# EC.net
KiCad netlist of a schematic drawn in EAGLE
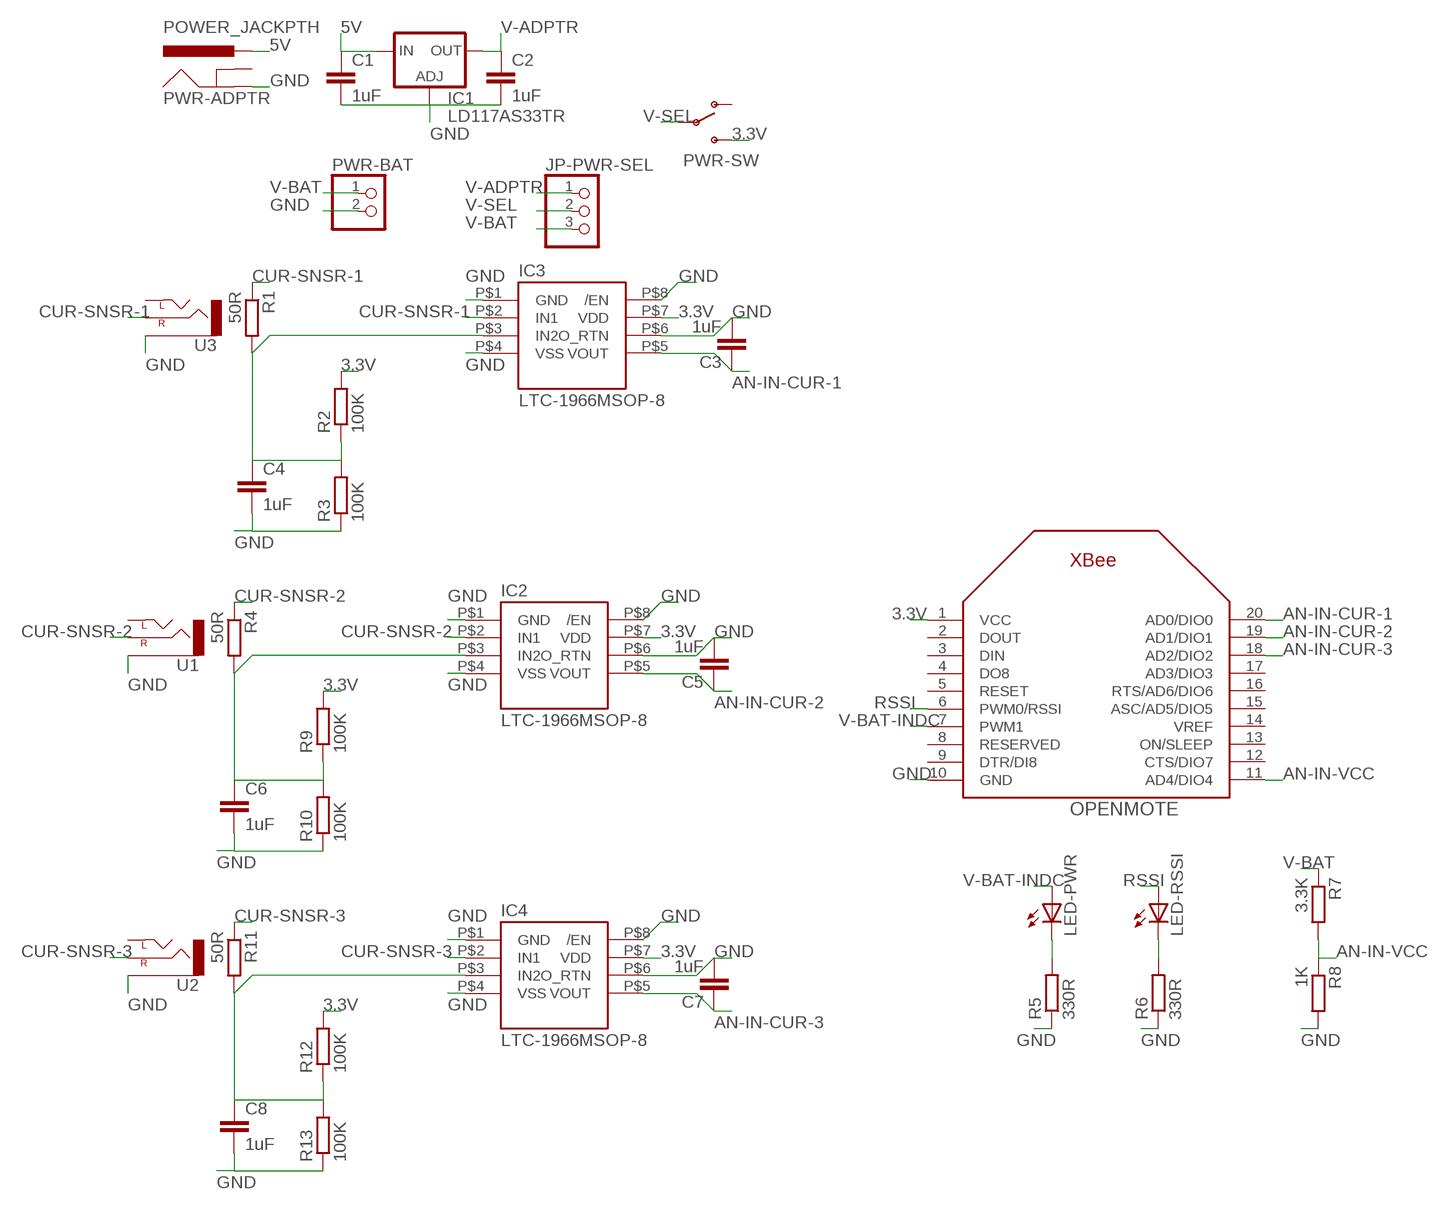
[diagram p0: schematic, sheet 1]

(export (version "E")
  (design (tool "Eeschema 10.0.6"))
  (components
    (comp (ref "C1")
      (value "1uF")
      (footprint "eagle-import:C0805")
      (libsource (lib "eagle-import") (part "C-EUC0805"))
    )
    (comp (ref "C2")
      (value "1uF")
      (footprint "eagle-import:C0805")
      (libsource (lib "eagle-import") (part "C-EUC0805"))
    )
    (comp (ref "C3")
      (value "1uF")
      (footprint "eagle-import:C0805")
      (libsource (lib "eagle-import") (part "C-EUC0805"))
    )
    (comp (ref "C4")
      (value "1uF")
      (footprint "eagle-import:C0805")
      (libsource (lib "eagle-import") (part "C-EUC0805"))
    )
    (comp (ref "C5")
      (value "1uF")
      (footprint "eagle-import:C0805")
      (libsource (lib "eagle-import") (part "C-EUC0805"))
    )
    (comp (ref "C6")
      (value "1uF")
      (footprint "eagle-import:C0805")
      (libsource (lib "eagle-import") (part "C-EUC0805"))
    )
    (comp (ref "C7")
      (value "1uF")
      (footprint "eagle-import:C0805")
      (libsource (lib "eagle-import") (part "C-EUC0805"))
    )
    (comp (ref "C8")
      (value "1uF")
      (footprint "eagle-import:C0805")
      (libsource (lib "eagle-import") (part "C-EUC0805"))
    )
    (comp (ref "IC1")
      (value "LD117AS33TR")
      (footprint "eagle-import:SOT223")
      (libsource (lib "eagle-import") (part "LD117A?S33TR"))
    )
    (comp (ref "IC2")
      (value "LTC-1966MSOP-8")
      (footprint "eagle-import:MSOP-8")
      (libsource (lib "eagle-import") (part "LTC-1966MSOP-8"))
    )
    (comp (ref "IC3")
      (value "LTC-1966MSOP-8")
      (footprint "eagle-import:MSOP-8")
      (libsource (lib "eagle-import") (part "LTC-1966MSOP-8"))
    )
    (comp (ref "IC4")
      (value "LTC-1966MSOP-8")
      (footprint "eagle-import:MSOP-8")
      (libsource (lib "eagle-import") (part "LTC-1966MSOP-8"))
    )
    (comp (ref "JP-PWR-SEL")
      (value "PINHD-1X3")
      (footprint "eagle-import:1X03")
      (libsource (lib "eagle-import") (part "PINHD-1X3"))
    )
    (comp (ref "LED-PWR")
      (value "LED0603")
      (footprint "eagle-import:LED-0603")
      (libsource (lib "eagle-import") (part "LED0603"))
    )
    (comp (ref "LED-RSSI")
      (value "LED0603")
      (footprint "eagle-import:LED-0603")
      (libsource (lib "eagle-import") (part "LED0603"))
    )
    (comp (ref "OPENMOTE")
      (value "XBEE")
      (footprint "eagle-import:XBEE")
      (libsource (lib "eagle-import") (part "XBEE"))
    )
    (comp (ref "PWR-ADPTR")
      (value "POWER_JACKPTH")
      (footprint "eagle-import:POWER_JACK_PTH")
      (libsource (lib "eagle-import") (part "POWER_JACKPTH"))
    )
    (comp (ref "PWR-BAT")
      (value "PINHD-1X2")
      (footprint "eagle-import:1X02")
      (libsource (lib "eagle-import") (part "PINHD-1X2"))
    )
    (comp (ref "PWR-SW")
      (value "SWITCH-SPDTSMD2")
      (footprint "eagle-import:SWITCH-SPDT-SMD")
      (libsource (lib "eagle-import") (part "SWITCH-SPDTSMD2"))
    )
    (comp (ref "R1")
      (value "50R")
      (footprint "eagle-import:R0603")
      (libsource (lib "eagle-import") (part "R-EU_R0603"))
    )
    (comp (ref "R2")
      (value "100K")
      (footprint "eagle-import:R0603")
      (libsource (lib "eagle-import") (part "R-EU_R0603"))
    )
    (comp (ref "R3")
      (value "100K")
      (footprint "eagle-import:R0603")
      (libsource (lib "eagle-import") (part "R-EU_R0603"))
    )
    (comp (ref "R4")
      (value "50R")
      (footprint "eagle-import:R0603")
      (libsource (lib "eagle-import") (part "R-EU_R0603"))
    )
    (comp (ref "R5")
      (value "330R")
      (footprint "eagle-import:R0603")
      (libsource (lib "eagle-import") (part "R-EU_R0603"))
    )
    (comp (ref "R6")
      (value "330R")
      (footprint "eagle-import:R0603")
      (libsource (lib "eagle-import") (part "R-EU_R0603"))
    )
    (comp (ref "R7")
      (value "3.3K")
      (footprint "eagle-import:R0603")
      (libsource (lib "eagle-import") (part "R-EU_R0603"))
    )
    (comp (ref "R8")
      (value "1K")
      (footprint "eagle-import:R0603")
      (libsource (lib "eagle-import") (part "R-EU_R0603"))
    )
    (comp (ref "R9")
      (value "100K")
      (footprint "eagle-import:R0603")
      (libsource (lib "eagle-import") (part "R-EU_R0603"))
    )
    (comp (ref "R10")
      (value "100K")
      (footprint "eagle-import:R0603")
      (libsource (lib "eagle-import") (part "R-EU_R0603"))
    )
    (comp (ref "R11")
      (value "50R")
      (footprint "eagle-import:R0603")
      (libsource (lib "eagle-import") (part "R-EU_R0603"))
    )
    (comp (ref "R12")
      (value "100K")
      (footprint "eagle-import:R0603")
      (libsource (lib "eagle-import") (part "R-EU_R0603"))
    )
    (comp (ref "R13")
      (value "100K")
      (footprint "eagle-import:R0603")
      (libsource (lib "eagle-import") (part "R-EU_R0603"))
    )
    (comp (ref "U1")
      (value "AUDIO-JACKSMD2")
      (footprint "eagle-import:AUDIO-JACK-3.5MM-SMD")
      (libsource (lib "eagle-import") (part "AUDIO-JACKSMD2"))
    )
    (comp (ref "U2")
      (value "AUDIO-JACKSMD2")
      (footprint "eagle-import:AUDIO-JACK-3.5MM-SMD")
      (libsource (lib "eagle-import") (part "AUDIO-JACKSMD2"))
    )
    (comp (ref "U3")
      (value "AUDIO-JACKSMD2")
      (footprint "eagle-import:AUDIO-JACK-3.5MM-SMD")
      (libsource (lib "eagle-import") (part "AUDIO-JACKSMD2"))
    )
  )
  (nets
    (net (code "1") (name "/3.3V") (class "Default")
      (node (ref "IC2") (pin "P$7") (pinfunction "VDD_P$7") (pintype "bidirectional"))
      (node (ref "IC3") (pin "P$7") (pinfunction "VDD_P$7") (pintype "bidirectional"))
      (node (ref "IC4") (pin "P$7") (pinfunction "VDD_P$7") (pintype "bidirectional"))
      (node (ref "OPENMOTE") (pin "1") (pinfunction "VCC_1") (pintype "power_in"))
      (node (ref "PWR-SW") (pin "3") (pinfunction "S_3") (pintype "passive"))
      (node (ref "R12") (pin "2") (pinfunction "2_2") (pintype "passive"))
      (node (ref "R2") (pin "2") (pinfunction "2_2") (pintype "passive"))
      (node (ref "R9") (pin "2") (pinfunction "2_2") (pintype "passive"))
    )
    (net (code "2") (name "/5V") (class "Default")
      (node (ref "C1") (pin "1") (pinfunction "1_1") (pintype "passive"))
      (node (ref "IC1") (pin "3") (pinfunction "IN_3") (pintype "input"))
      (node (ref "PWR-ADPTR") (pin "PWR") (pinfunction "PWR_PWR") (pintype "bidirectional"))
    )
    (net (code "3") (name "/AN-IN-CUR-1") (class "Default")
      (node (ref "C3") (pin "1") (pinfunction "1_1") (pintype "passive"))
      (node (ref "IC3") (pin "P$5") (pinfunction "VOUT_P$5") (pintype "bidirectional"))
      (node (ref "OPENMOTE") (pin "20") (pinfunction "AD0/DIO0_20") (pintype "bidirectional"))
    )
    (net (code "4") (name "/AN-IN-CUR-2") (class "Default")
      (node (ref "C5") (pin "1") (pinfunction "1_1") (pintype "passive"))
      (node (ref "IC2") (pin "P$5") (pinfunction "VOUT_P$5") (pintype "bidirectional"))
      (node (ref "OPENMOTE") (pin "19") (pinfunction "AD1/DIO1_19") (pintype "bidirectional"))
    )
    (net (code "5") (name "/AN-IN-CUR-3") (class "Default")
      (node (ref "C7") (pin "1") (pinfunction "1_1") (pintype "passive"))
      (node (ref "IC4") (pin "P$5") (pinfunction "VOUT_P$5") (pintype "bidirectional"))
      (node (ref "OPENMOTE") (pin "18") (pinfunction "AD2/DIO2_18") (pintype "bidirectional"))
    )
    (net (code "6") (name "/AN-IN-VCC") (class "Default")
      (node (ref "OPENMOTE") (pin "11") (pinfunction "AD4/DIO4_11") (pintype "bidirectional"))
      (node (ref "R7") (pin "2") (pinfunction "2_2") (pintype "passive"))
      (node (ref "R8") (pin "1") (pinfunction "1_1") (pintype "passive"))
    )
    (net (code "7") (name "/CUR-SNSR-1") (class "Default")
      (node (ref "IC3") (pin "P$2") (pinfunction "IN1_P$2") (pintype "bidirectional"))
      (node (ref "R1") (pin "1") (pinfunction "1_1") (pintype "passive"))
      (node (ref "U3") (pin "RING") (pinfunction "RIGHT_RING") (pintype "bidirectional"))
    )
    (net (code "8") (name "/CUR-SNSR-2") (class "Default")
      (node (ref "IC2") (pin "P$2") (pinfunction "IN1_P$2") (pintype "bidirectional"))
      (node (ref "R4") (pin "1") (pinfunction "1_1") (pintype "passive"))
      (node (ref "U1") (pin "RING") (pinfunction "RIGHT_RING") (pintype "bidirectional"))
    )
    (net (code "9") (name "/CUR-SNSR-3") (class "Default")
      (node (ref "IC4") (pin "P$2") (pinfunction "IN1_P$2") (pintype "bidirectional"))
      (node (ref "R11") (pin "1") (pinfunction "1_1") (pintype "passive"))
      (node (ref "U2") (pin "RING") (pinfunction "RIGHT_RING") (pintype "bidirectional"))
    )
    (net (code "10") (name "/GND") (class "Default")
      (node (ref "C1") (pin "2") (pinfunction "2_2") (pintype "passive"))
      (node (ref "C2") (pin "2") (pinfunction "2_2") (pintype "passive"))
      (node (ref "C3") (pin "2") (pinfunction "2_2") (pintype "passive"))
      (node (ref "C4") (pin "2") (pinfunction "2_2") (pintype "passive"))
      (node (ref "C5") (pin "2") (pinfunction "2_2") (pintype "passive"))
      (node (ref "C6") (pin "2") (pinfunction "2_2") (pintype "passive"))
      (node (ref "C7") (pin "2") (pinfunction "2_2") (pintype "passive"))
      (node (ref "C8") (pin "2") (pinfunction "2_2") (pintype "passive"))
      (node (ref "IC1") (pin "1") (pinfunction "ADJ_1") (pintype "input"))
      (node (ref "IC2") (pin "P$1") (pinfunction "GND_P$1") (pintype "bidirectional"))
      (node (ref "IC2") (pin "P$4") (pinfunction "VSS_P$4") (pintype "bidirectional"))
      (node (ref "IC2") (pin "P$6") (pinfunction "O_RTN_P$6") (pintype "bidirectional"))
      (node (ref "IC2") (pin "P$8") (pinfunction "/EN_P$8") (pintype "bidirectional"))
      (node (ref "IC3") (pin "P$1") (pinfunction "GND_P$1") (pintype "bidirectional"))
      (node (ref "IC3") (pin "P$4") (pinfunction "VSS_P$4") (pintype "bidirectional"))
      (node (ref "IC3") (pin "P$6") (pinfunction "O_RTN_P$6") (pintype "bidirectional"))
      (node (ref "IC3") (pin "P$8") (pinfunction "/EN_P$8") (pintype "bidirectional"))
      (node (ref "IC4") (pin "P$1") (pinfunction "GND_P$1") (pintype "bidirectional"))
      (node (ref "IC4") (pin "P$4") (pinfunction "VSS_P$4") (pintype "bidirectional"))
      (node (ref "IC4") (pin "P$6") (pinfunction "O_RTN_P$6") (pintype "bidirectional"))
      (node (ref "IC4") (pin "P$8") (pinfunction "/EN_P$8") (pintype "bidirectional"))
      (node (ref "OPENMOTE") (pin "10") (pinfunction "GND_10") (pintype "power_in"))
      (node (ref "PWR-ADPTR") (pin "GND") (pinfunction "GND_GND") (pintype "bidirectional"))
      (node (ref "PWR-BAT") (pin "2") (pinfunction "2_2") (pintype "passive"))
      (node (ref "R10") (pin "1") (pinfunction "1_1") (pintype "passive"))
      (node (ref "R13") (pin "1") (pinfunction "1_1") (pintype "passive"))
      (node (ref "R3") (pin "1") (pinfunction "1_1") (pintype "passive"))
      (node (ref "R5") (pin "1") (pinfunction "1_1") (pintype "passive"))
      (node (ref "R6") (pin "1") (pinfunction "1_1") (pintype "passive"))
      (node (ref "R8") (pin "2") (pinfunction "2_2") (pintype "passive"))
      (node (ref "U1") (pin "SLEEVE") (pinfunction "SLEEVE_SLEEVE") (pintype "bidirectional"))
      (node (ref "U2") (pin "SLEEVE") (pinfunction "SLEEVE_SLEEVE") (pintype "bidirectional"))
      (node (ref "U3") (pin "SLEEVE") (pinfunction "SLEEVE_SLEEVE") (pintype "bidirectional"))
    )
    (net (code "11") (name "/RSSI") (class "Default")
      (node (ref "LED-RSSI") (pin "A") (pinfunction "A_A") (pintype "passive"))
      (node (ref "OPENMOTE") (pin "6") (pinfunction "PWM0/RSSI_6") (pintype "output"))
    )
    (net (code "12") (name "/V-ADPTR") (class "Default")
      (node (ref "C2") (pin "1") (pinfunction "1_1") (pintype "passive"))
      (node (ref "IC1") (pin "4") (pinfunction "OUT_4") (pintype "passive"))
      (node (ref "JP-PWR-SEL") (pin "1") (pinfunction "1_1") (pintype "passive"))
    )
    (net (code "13") (name "/V-BAT") (class "Default")
      (node (ref "JP-PWR-SEL") (pin "3") (pinfunction "3_3") (pintype "passive"))
      (node (ref "PWR-BAT") (pin "1") (pinfunction "1_1") (pintype "passive"))
      (node (ref "R7") (pin "1") (pinfunction "1_1") (pintype "passive"))
    )
    (net (code "14") (name "/V-BAT-INDC") (class "Default")
      (node (ref "LED-PWR") (pin "A") (pinfunction "A_A") (pintype "passive"))
      (node (ref "OPENMOTE") (pin "7") (pinfunction "PWM1_7") (pintype "output"))
    )
    (net (code "15") (name "/V-SEL") (class "Default")
      (node (ref "JP-PWR-SEL") (pin "2") (pinfunction "2_2") (pintype "passive"))
      (node (ref "PWR-SW") (pin "2") (pinfunction "P_2") (pintype "passive"))
    )
    (net (code "16") (name "Net-(IC2-IN2)") (class "Default")
      (node (ref "C6") (pin "1") (pinfunction "1_1") (pintype "passive"))
      (node (ref "IC2") (pin "P$3") (pinfunction "IN2_P$3") (pintype "bidirectional"))
      (node (ref "R10") (pin "2") (pinfunction "2_2") (pintype "passive"))
      (node (ref "R4") (pin "2") (pinfunction "2_2") (pintype "passive"))
      (node (ref "R9") (pin "1") (pinfunction "1_1") (pintype "passive"))
    )
    (net (code "17") (name "Net-(IC3-IN2)") (class "Default")
      (node (ref "C4") (pin "1") (pinfunction "1_1") (pintype "passive"))
      (node (ref "IC3") (pin "P$3") (pinfunction "IN2_P$3") (pintype "bidirectional"))
      (node (ref "R1") (pin "2") (pinfunction "2_2") (pintype "passive"))
      (node (ref "R2") (pin "1") (pinfunction "1_1") (pintype "passive"))
      (node (ref "R3") (pin "2") (pinfunction "2_2") (pintype "passive"))
    )
    (net (code "18") (name "Net-(IC4-IN2)") (class "Default")
      (node (ref "C8") (pin "1") (pinfunction "1_1") (pintype "passive"))
      (node (ref "IC4") (pin "P$3") (pinfunction "IN2_P$3") (pintype "bidirectional"))
      (node (ref "R11") (pin "2") (pinfunction "2_2") (pintype "passive"))
      (node (ref "R12") (pin "1") (pinfunction "1_1") (pintype "passive"))
      (node (ref "R13") (pin "2") (pinfunction "2_2") (pintype "passive"))
    )
    (net (code "19") (name "Net-(LED-PWR-PadC)") (class "Default")
      (node (ref "LED-PWR") (pin "C") (pinfunction "C_C") (pintype "passive"))
      (node (ref "R5") (pin "2") (pinfunction "2_2") (pintype "passive"))
    )
    (net (code "20") (name "Net-(LED-RSSI-PadC)") (class "Default")
      (node (ref "LED-RSSI") (pin "C") (pinfunction "C_C") (pintype "passive"))
      (node (ref "R6") (pin "2") (pinfunction "2_2") (pintype "passive"))
    )
    (net (code "21") (name "unconnected-(OPENMOTE-AD3{slash}DIO3-Pad17)") (class "Default")
      (node (ref "OPENMOTE") (pin "17") (pinfunction "AD3/DIO3_17") (pintype "bidirectional"))
    )
    (net (code "22") (name "unconnected-(OPENMOTE-ASC{slash}AD5{slash}DIO5-Pad15)") (class "Default")
      (node (ref "OPENMOTE") (pin "15") (pinfunction "ASC/AD5/DIO5_15") (pintype "bidirectional"))
    )
    (net (code "23") (name "unconnected-(OPENMOTE-CTS{slash}DIO7-Pad12)") (class "Default")
      (node (ref "OPENMOTE") (pin "12") (pinfunction "CTS/DIO7_12") (pintype "bidirectional"))
    )
    (net (code "24") (name "unconnected-(OPENMOTE-DIN-Pad3)") (class "Default")
      (node (ref "OPENMOTE") (pin "3") (pinfunction "DIN_3") (pintype "input"))
    )
    (net (code "25") (name "unconnected-(OPENMOTE-DO8-Pad4)") (class "Default")
      (node (ref "OPENMOTE") (pin "4") (pinfunction "DO8_4") (pintype "output"))
    )
    (net (code "26") (name "unconnected-(OPENMOTE-DOUT-Pad2)") (class "Default")
      (node (ref "OPENMOTE") (pin "2") (pinfunction "DOUT_2") (pintype "output"))
    )
    (net (code "27") (name "unconnected-(OPENMOTE-DTR{slash}DI8-Pad9)") (class "Default")
      (node (ref "OPENMOTE") (pin "9") (pinfunction "DTR/DI8_9") (pintype "input"))
    )
    (net (code "28") (name "unconnected-(OPENMOTE-ON{slash}SLEEP-Pad13)") (class "Default")
      (node (ref "OPENMOTE") (pin "13") (pinfunction "ON/SLEEP_13") (pintype "output"))
    )
    (net (code "29") (name "unconnected-(OPENMOTE-RESERVED-Pad8)") (class "Default")
      (node (ref "OPENMOTE") (pin "8") (pinfunction "RESERVED_8") (pintype "no_connect"))
    )
    (net (code "30") (name "unconnected-(OPENMOTE-RESET-Pad5)") (class "Default")
      (node (ref "OPENMOTE") (pin "5") (pinfunction "RESET_5") (pintype "input"))
    )
    (net (code "31") (name "unconnected-(OPENMOTE-RTS{slash}AD6{slash}DIO6-Pad16)") (class "Default")
      (node (ref "OPENMOTE") (pin "16") (pinfunction "RTS/AD6/DIO6_16") (pintype "bidirectional"))
    )
    (net (code "32") (name "unconnected-(OPENMOTE-VREF-Pad14)") (class "Default")
      (node (ref "OPENMOTE") (pin "14") (pinfunction "VREF_14") (pintype "input"))
    )
    (net (code "33") (name "unconnected-(PWR-ADPTR-PadGNDBREAK)") (class "Default")
      (node (ref "PWR-ADPTR") (pin "GNDBREAK") (pinfunction "GNDBREAK_GNDBREAK") (pintype "bidirectional"))
    )
    (net (code "34") (name "unconnected-(PWR-SW-O-Pad1)") (class "Default")
      (node (ref "PWR-SW") (pin "1") (pinfunction "O_1") (pintype "passive"))
    )
    (net (code "35") (name "unconnected-(U1-LEFT-PadTIP)") (class "Default")
      (node (ref "U1") (pin "TIP") (pinfunction "LEFT_TIP") (pintype "bidirectional"))
    )
    (net (code "36") (name "unconnected-(U2-LEFT-PadTIP)") (class "Default")
      (node (ref "U2") (pin "TIP") (pinfunction "LEFT_TIP") (pintype "bidirectional"))
    )
    (net (code "37") (name "unconnected-(U3-LEFT-PadTIP)") (class "Default")
      (node (ref "U3") (pin "TIP") (pinfunction "LEFT_TIP") (pintype "bidirectional"))
    )
  )
)
